# GTM_I2Cconnector.net
KiCad netlist of a schematic drawn in Altium Designer
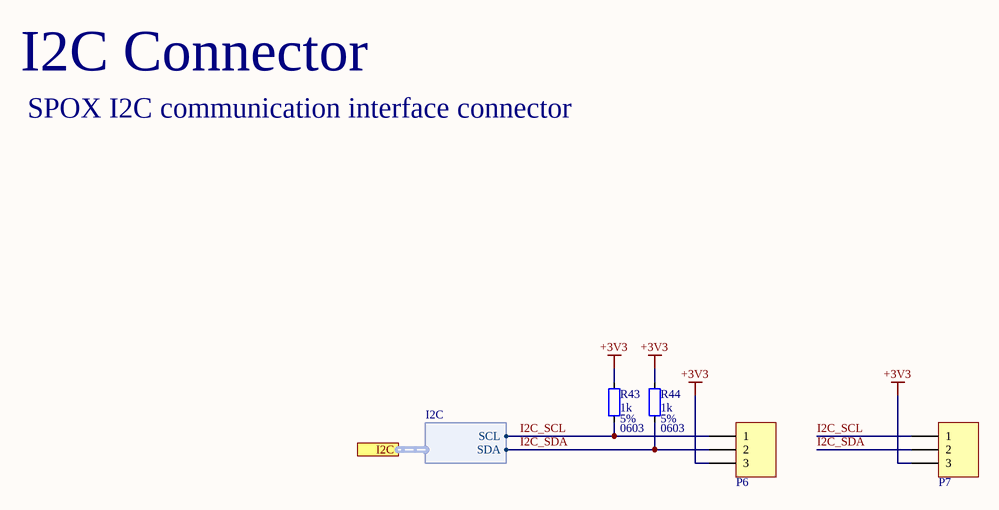
[diagram p0: GTM_I2Cconnector.SchDoc]

(export (version "E")
  (design (tool "Eeschema 10.0.6"))
  (components
    (comp (ref "P6")
      (value "HDR1X3")
      (footprint "Molex SPOX Horizontal 3 Circuits")
      (description "Header, 3-Pin")
      (fields (field (name "PUBLISHER") "Altium Limited"))
      (libsource (lib "Library_Altium_KNR") (part "HDR1X3"))
    )
    (comp (ref "P7")
      (value "HDR1X3")
      (footprint "Molex SPOX Horizontal 3 Circuits")
      (description "Doubled Ceonnector")
      (fields (field (name "PUBLISHER") "Altium Limited"))
      (libsource (lib "Library_Altium_KNR") (part "HDR1X3"))
    )
    (comp (ref "R43")
      (value "1k")
      (footprint "0603")
      (description "Resistior")
      (fields (field (name "TOLERANCE") "5%") (field (name "PACKAGE") "0603"))
      (libsource (lib "Library_Altium_KNR") (part "RES"))
    )
    (comp (ref "R44")
      (value "1k")
      (footprint "0603")
      (description "Resistior")
      (fields (field (name "TOLERANCE") "5%") (field (name "PACKAGE") "0603"))
      (libsource (lib "Library_Altium_KNR") (part "RES"))
    )
  )
  (nets
    (net (code "2") (name "+3V3") (class "Default")
      (node (ref "P6") (pin "3") (pinfunction "3_3") (pintype "passive"))
      (node (ref "P7") (pin "3") (pinfunction "3_3") (pintype "passive"))
      (node (ref "R43") (pin "2") (pinfunction "2_2") (pintype "passive"))
      (node (ref "R44") (pin "2") (pinfunction "2_2") (pintype "passive"))
    )
    (net (code "3") (name "/I2C_SCL") (class "Default")
      (node (ref "P6") (pin "1") (pinfunction "1_1") (pintype "passive"))
      (node (ref "P7") (pin "1") (pinfunction "1_1") (pintype "passive"))
      (node (ref "R43") (pin "1") (pinfunction "1_1") (pintype "passive"))
    )
    (net (code "4") (name "/I2C_SDA") (class "Default")
      (node (ref "P6") (pin "2") (pinfunction "2_2") (pintype "passive"))
      (node (ref "P7") (pin "2") (pinfunction "2_2") (pintype "passive"))
      (node (ref "R44") (pin "1") (pinfunction "1_1") (pintype "passive"))
    )
  )
)
